# ADC.net
KiCad netlist of a schematic drawn in Altium Designer
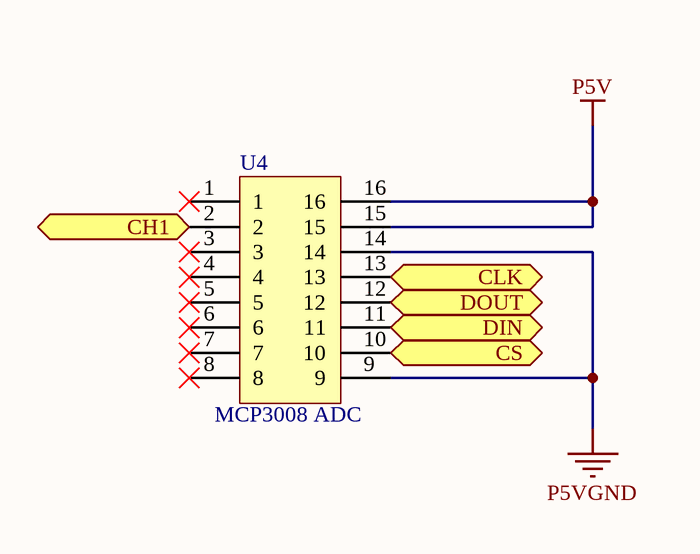
[diagram p0: ADC.SchDoc]

(export (version "E")
  (design (tool "Eeschema 10.0.6"))
  (components
    (comp (ref "U4")
      (value "MCP3008 ADC")
      (footprint "ISDIP16_LGE1.0")
      (description "16-pin DIP socket")
      (fields (field (name "PUBLISHER") "Altium Limited"))
      (libsource (lib "PartsDatabaseV13p4") (part "G-DIP16"))
    )
  )
  (nets
    (net (code "1") (name "/CH1") (class "Default")
      (node (ref "U4") (pin "2") (pinfunction "2_2") (pintype "passive"))
    )
    (net (code "2") (name "/CLK") (class "Default")
      (node (ref "U4") (pin "13") (pinfunction "13_13") (pintype "passive"))
    )
    (net (code "3") (name "/CS") (class "Default")
      (node (ref "U4") (pin "10") (pinfunction "10_10") (pintype "passive"))
    )
    (net (code "4") (name "/DIN") (class "Default")
      (node (ref "U4") (pin "11") (pinfunction "11_11") (pintype "passive"))
    )
    (net (code "5") (name "/DOUT") (class "Default")
      (node (ref "U4") (pin "12") (pinfunction "12_12") (pintype "passive"))
    )
    (net (code "6") (name "P5V") (class "Default")
      (node (ref "U4") (pin "15") (pinfunction "15_15") (pintype "passive"))
      (node (ref "U4") (pin "16") (pinfunction "16_16") (pintype "passive"))
    )
    (net (code "7") (name "P5VGND") (class "Default")
      (node (ref "U4") (pin "14") (pinfunction "14_14") (pintype "passive"))
      (node (ref "U4") (pin "9") (pinfunction "9_9") (pintype "passive"))
    )
    (net (code "8") (name "unconnected-(U4-Pad1)") (class "Default")
      (node (ref "U4") (pin "1") (pinfunction "1_1") (pintype "passive+no_connect"))
    )
    (net (code "9") (name "unconnected-(U4-Pad3)") (class "Default")
      (node (ref "U4") (pin "3") (pinfunction "3_3") (pintype "passive+no_connect"))
    )
    (net (code "10") (name "unconnected-(U4-Pad4)") (class "Default")
      (node (ref "U4") (pin "4") (pinfunction "4_4") (pintype "passive+no_connect"))
    )
    (net (code "11") (name "unconnected-(U4-Pad5)") (class "Default")
      (node (ref "U4") (pin "5") (pinfunction "5_5") (pintype "passive+no_connect"))
    )
    (net (code "12") (name "unconnected-(U4-Pad6)") (class "Default")
      (node (ref "U4") (pin "6") (pinfunction "6_6") (pintype "passive+no_connect"))
    )
    (net (code "13") (name "unconnected-(U4-Pad7)") (class "Default")
      (node (ref "U4") (pin "7") (pinfunction "7_7") (pintype "passive+no_connect"))
    )
    (net (code "14") (name "unconnected-(U4-Pad8)") (class "Default")
      (node (ref "U4") (pin "8") (pinfunction "8_8") (pintype "passive+no_connect"))
    )
  )
)
